# iv12-driver-board-v1b.net
KiCad netlist of a schematic drawn in EAGLE
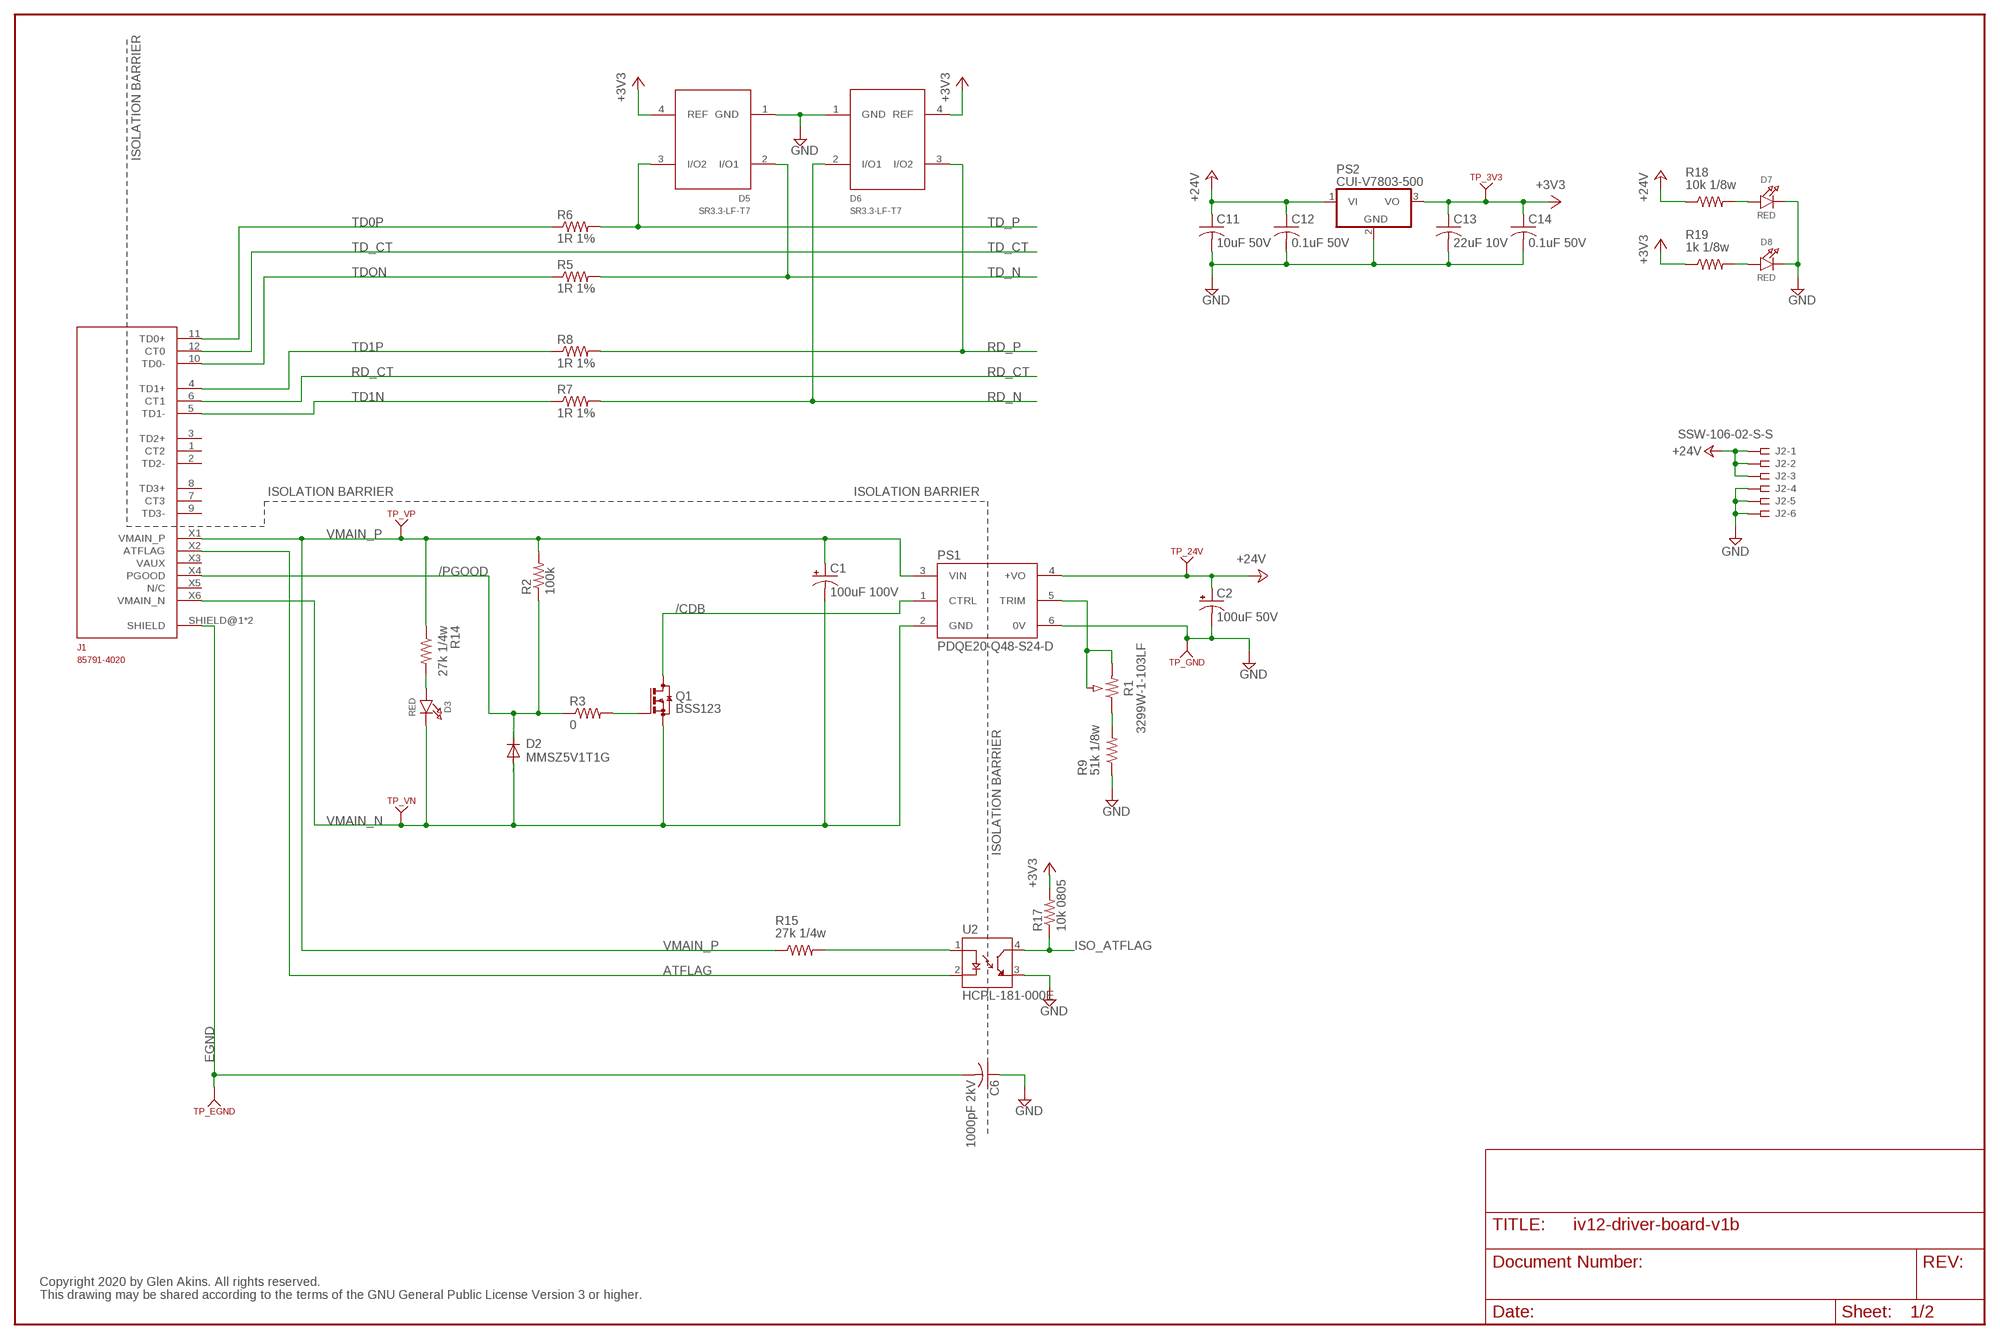
[diagram p0: schematic, sheet 1]
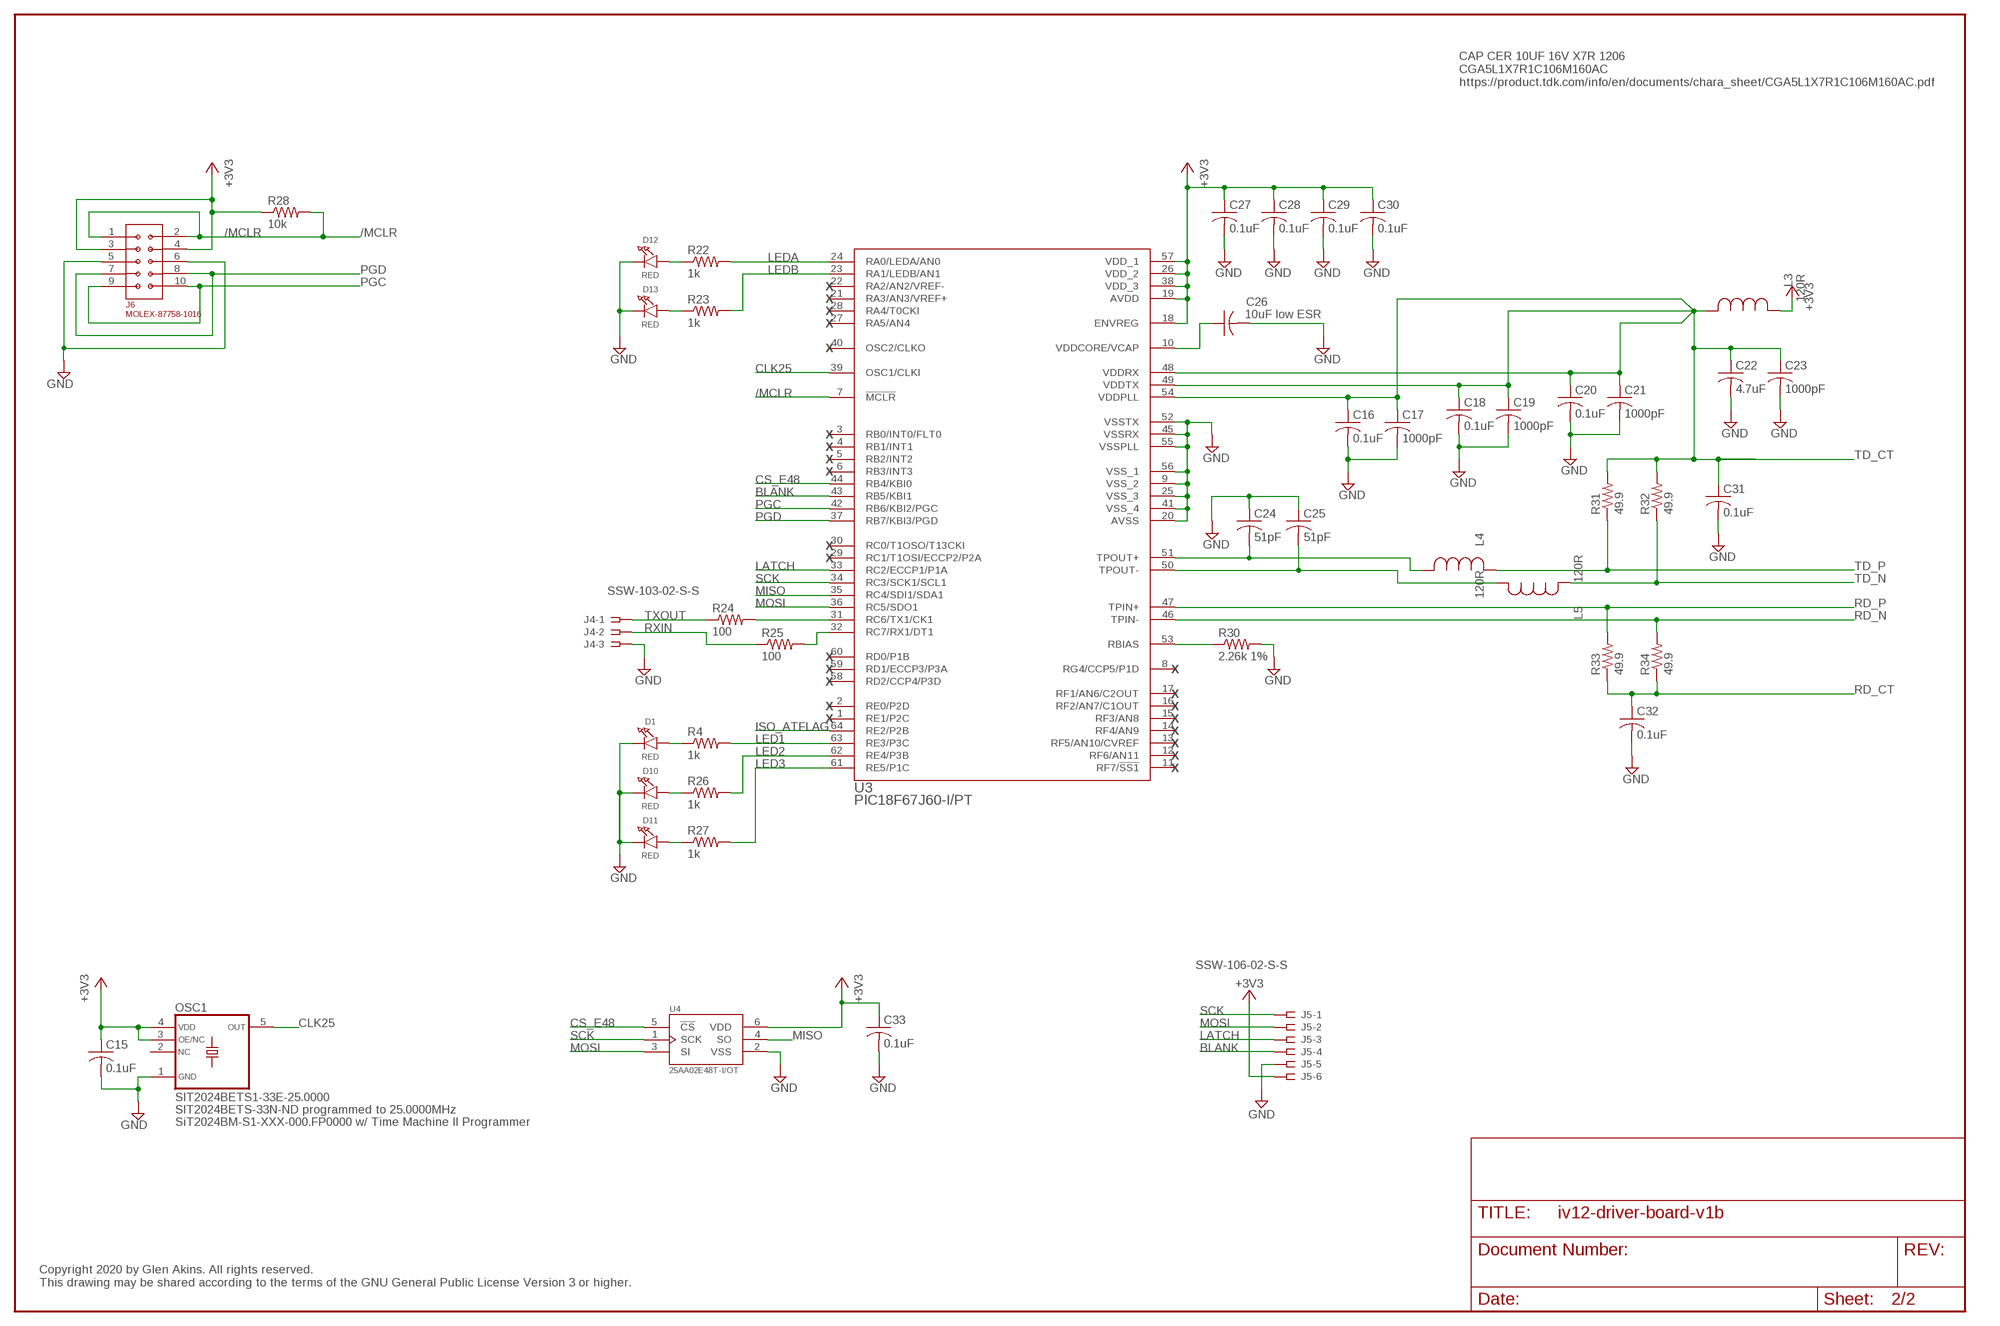
[diagram p1: schematic, sheet 2]

(export (version "E")
  (design (tool "Eeschema 10.0.6"))
  (components
    (comp (ref "C15")
      (value "0.1uF")
      (footprint "eagle-import:C0603")
      (libsource (lib "eagle-import") (part "C-USC0603"))
    )
    (comp (ref "C16")
      (value "0.1uF")
      (footprint "eagle-import:C0805")
      (libsource (lib "eagle-import") (part "C-USC0805"))
    )
    (comp (ref "C17")
      (value "1000pF")
      (footprint "eagle-import:C0805")
      (libsource (lib "eagle-import") (part "C-USC0805"))
    )
    (comp (ref "C18")
      (value "0.1uF")
      (footprint "eagle-import:C0805")
      (libsource (lib "eagle-import") (part "C-USC0805"))
    )
    (comp (ref "C19")
      (value "1000pF")
      (footprint "eagle-import:C0805")
      (libsource (lib "eagle-import") (part "C-USC0805"))
    )
    (comp (ref "C20")
      (value "0.1uF")
      (footprint "eagle-import:C0805")
      (libsource (lib "eagle-import") (part "C-USC0805"))
    )
    (comp (ref "C21")
      (value "1000pF")
      (footprint "eagle-import:C0805")
      (libsource (lib "eagle-import") (part "C-USC0805"))
    )
    (comp (ref "C22")
      (value "4.7uF")
      (footprint "eagle-import:C0805")
      (libsource (lib "eagle-import") (part "C-USC0805"))
    )
    (comp (ref "C23")
      (value "1000pF")
      (footprint "eagle-import:C0805")
      (libsource (lib "eagle-import") (part "C-USC0805"))
    )
    (comp (ref "C24")
      (value "51pF")
      (footprint "eagle-import:C0805")
      (libsource (lib "eagle-import") (part "C-USC0805"))
    )
    (comp (ref "C25")
      (value "51pF")
      (footprint "eagle-import:C0805")
      (libsource (lib "eagle-import") (part "C-USC0805"))
    )
    (comp (ref "C26")
      (value "10uF low ESR")
      (footprint "eagle-import:C1206")
      (libsource (lib "eagle-import") (part "resistor_C-USC1206"))
    )
    (comp (ref "C27")
      (value "0.1uF")
      (footprint "eagle-import:C0603")
      (libsource (lib "eagle-import") (part "C-USC0603"))
    )
    (comp (ref "C28")
      (value "0.1uF")
      (footprint "eagle-import:C0603")
      (libsource (lib "eagle-import") (part "C-USC0603"))
    )
    (comp (ref "C29")
      (value "0.1uF")
      (footprint "eagle-import:C0603")
      (libsource (lib "eagle-import") (part "C-USC0603"))
    )
    (comp (ref "C30")
      (value "0.1uF")
      (footprint "eagle-import:C0603")
      (libsource (lib "eagle-import") (part "C-USC0603"))
    )
    (comp (ref "C31")
      (value "0.1uF")
      (footprint "eagle-import:C0805")
      (libsource (lib "eagle-import") (part "C-USC0805"))
    )
    (comp (ref "C32")
      (value "0.1uF")
      (footprint "eagle-import:C0805")
      (libsource (lib "eagle-import") (part "C-USC0805"))
    )
    (comp (ref "C33")
      (value "0.1uF")
      (footprint "eagle-import:C0603")
      (libsource (lib "eagle-import") (part "C-USC0603"))
    )
    (comp (ref "D1")
      (value "RED")
      (footprint "eagle-import:CHIPLED_0805_NOOUTLINE")
      (libsource (lib "eagle-import") (part "LED0805_NOOUTLINE"))
    )
    (comp (ref "D10")
      (value "RED")
      (footprint "eagle-import:CHIPLED_0805_NOOUTLINE")
      (libsource (lib "eagle-import") (part "LED0805_NOOUTLINE"))
    )
    (comp (ref "D11")
      (value "RED")
      (footprint "eagle-import:CHIPLED_0805_NOOUTLINE")
      (libsource (lib "eagle-import") (part "LED0805_NOOUTLINE"))
    )
    (comp (ref "D12")
      (value "RED")
      (footprint "eagle-import:CHIPLED_0805_NOOUTLINE")
      (libsource (lib "eagle-import") (part "LED0805_NOOUTLINE"))
    )
    (comp (ref "D13")
      (value "RED")
      (footprint "eagle-import:CHIPLED_0805_NOOUTLINE")
      (libsource (lib "eagle-import") (part "LED0805_NOOUTLINE"))
    )
    (comp (ref "J4")
      (value "SSW-103-02-S-S")
      (footprint "eagle-import:SSW-103-02-S-S")
      (libsource (lib "eagle-import") (part "SSW-103-02-S-S"))
    )
    (comp (ref "J5")
      (value "SSW-106-02-S-S")
      (footprint "eagle-import:SSW-106-02-S-S")
      (libsource (lib "eagle-import") (part "SSW-106-02-S-S"))
    )
    (comp (ref "J6")
      (value "MOLEX-87758-1016")
      (footprint "eagle-import:CON-2MM-2X5")
      (fields (field (name "MFR") "MOLEX") (field (name "MFR_PART_NO") "87758-1016"))
      (libsource (lib "eagle-import") (part "CON-2MM-2X5-MOLEX-87758-1016"))
    )
    (comp (ref "L3")
      (value "120R")
      (footprint "eagle-import:IND_1608-M")
      (fields (field (name "MANUFACTURER_PART_NUMBER") "MMZ1608B121CTAH0"))
      (libsource (lib "eagle-import") (part "MMZ1608B121CTAH0IND_1608-M"))
    )
    (comp (ref "L4")
      (value "120R")
      (footprint "eagle-import:IND_1608-M")
      (fields (field (name "MANUFACTURER_PART_NUMBER") "MMZ1608B121CTAH0"))
      (libsource (lib "eagle-import") (part "MMZ1608B121CTAH0IND_1608-M"))
    )
    (comp (ref "L5")
      (value "120R")
      (footprint "eagle-import:IND_1608-M")
      (fields (field (name "MANUFACTURER_PART_NUMBER") "MMZ1608B121CTAH0"))
      (libsource (lib "eagle-import") (part "MMZ1608B121CTAH0IND_1608-M"))
    )
    (comp (ref "OSC1")
      (value "SIT2024BETS1-33E-25.0000")
      (footprint "eagle-import:SOT23-5")
      (libsource (lib "eagle-import") (part "SIT2024BETS1-33E-10.0000"))
    )
    (comp (ref "R4")
      (value "1k")
      (footprint "eagle-import:R0805")
      (libsource (lib "eagle-import") (part "R-US_R0805"))
    )
    (comp (ref "R22")
      (value "1k")
      (footprint "eagle-import:R0805")
      (libsource (lib "eagle-import") (part "R-US_R0805"))
    )
    (comp (ref "R23")
      (value "1k")
      (footprint "eagle-import:R0805")
      (libsource (lib "eagle-import") (part "R-US_R0805"))
    )
    (comp (ref "R24")
      (value "100")
      (footprint "eagle-import:R0805")
      (libsource (lib "eagle-import") (part "R-US_R0805"))
    )
    (comp (ref "R25")
      (value "100")
      (footprint "eagle-import:R0805")
      (libsource (lib "eagle-import") (part "R-US_R0805"))
    )
    (comp (ref "R26")
      (value "1k")
      (footprint "eagle-import:R0805")
      (libsource (lib "eagle-import") (part "R-US_R0805"))
    )
    (comp (ref "R27")
      (value "1k")
      (footprint "eagle-import:R0805")
      (libsource (lib "eagle-import") (part "R-US_R0805"))
    )
    (comp (ref "R28")
      (value "10k")
      (footprint "eagle-import:R0805")
      (libsource (lib "eagle-import") (part "R-US_R0805"))
    )
    (comp (ref "R30")
      (value "2.26k 1%")
      (footprint "eagle-import:R0805")
      (libsource (lib "eagle-import") (part "R-US_R0805"))
    )
    (comp (ref "R31")
      (value "49.9")
      (footprint "eagle-import:R0805")
      (libsource (lib "eagle-import") (part "R-US_R0805"))
    )
    (comp (ref "R32")
      (value "49.9")
      (footprint "eagle-import:R0805")
      (libsource (lib "eagle-import") (part "R-US_R0805"))
    )
    (comp (ref "R33")
      (value "49.9")
      (footprint "eagle-import:R0805")
      (libsource (lib "eagle-import") (part "R-US_R0805"))
    )
    (comp (ref "R34")
      (value "49.9")
      (footprint "eagle-import:R0805")
      (libsource (lib "eagle-import") (part "R-US_R0805"))
    )
    (comp (ref "U3")
      (value "PIC18F67J60-I/PT")
      (footprint "eagle-import:TQFP64_10X10MC")
      (fields (field (name "MANUFACTURER_PART_NUMBER") "PIC18F67J60IPT"))
      (libsource (lib "eagle-import") (part "PIC18F67J60-I/PT"))
    )
    (comp (ref "U4")
      (value "25AA02E48T-I/OT")
      (footprint "eagle-import:SOT95P270X145-6N")
      (fields (field (name "DIGI-KEY_PART_NUMBER") "25AA02E48T-I/OTCT-ND") (field (name "MF") "Microchip"))
      (libsource (lib "eagle-import") (part "25AA02E48T-I/OT"))
    )
    (comp (ref "C1")
      (value "100uF 100V")
      (footprint "eagle-import:E5-13")
      (libsource (lib "eagle-import") (part "CPOL-USE5-13"))
    )
    (comp (ref "C2")
      (value "100uF 50V")
      (footprint "eagle-import:E5-10,5")
      (libsource (lib "eagle-import") (part "CPOL-USE5-10.5"))
    )
    (comp (ref "C6")
      (value "1000pF 2kV")
      (footprint "eagle-import:C1206K")
      (libsource (lib "eagle-import") (part "C-USC1206K"))
    )
    (comp (ref "C11")
      (value "10uF 50V")
      (footprint "eagle-import:C1210K")
      (fields (field (name "MFR") "KEMET") (field (name "MFR_PART_NO") "C1210C106K5RACTU"))
      (libsource (lib "eagle-import") (part "C-USC1210K"))
    )
    (comp (ref "C12")
      (value "0.1uF 50V")
      (footprint "eagle-import:C0805")
      (fields (field (name "MFR") "KEMET") (field (name "MFR_PART_NO") "C1206S104M5RACTU"))
      (libsource (lib "eagle-import") (part "C-USC0805"))
    )
    (comp (ref "C13")
      (value "22uF 10V")
      (footprint "eagle-import:C1206K")
      (fields (field (name "MFR") "KEMET") (field (name "MFR_PART_NO") "C1206C226K8RAC7800"))
      (libsource (lib "eagle-import") (part "C-USC1206K"))
    )
    (comp (ref "C14")
      (value "0.1uF 50V")
      (footprint "eagle-import:C0805")
      (fields (field (name "MFR") "KEMET") (field (name "MFR_PART_NO") "C1206S104M5RACTU"))
      (libsource (lib "eagle-import") (part "C-USC0805"))
    )
    (comp (ref "D2")
      (value "MMSZ5V1T1G")
      (footprint "eagle-import:SOD123")
      (libsource (lib "eagle-import") (part "DIODE-SOD123"))
    )
    (comp (ref "D3")
      (value "RED")
      (footprint "eagle-import:CHIPLED_0805_NOOUTLINE")
      (libsource (lib "eagle-import") (part "LED0805_NOOUTLINE"))
    )
    (comp (ref "D5")
      (value "SR3.3-LF-T7")
      (footprint "eagle-import:SOT143B")
      (libsource (lib "eagle-import") (part "SR3.3-LF-T7"))
    )
    (comp (ref "D6")
      (value "SR3.3-LF-T7")
      (footprint "eagle-import:SOT143B")
      (libsource (lib "eagle-import") (part "SR3.3-LF-T7"))
    )
    (comp (ref "D7")
      (value "RED")
      (footprint "eagle-import:CHIPLED_0805_NOOUTLINE")
      (libsource (lib "eagle-import") (part "LED0805_NOOUTLINE"))
    )
    (comp (ref "D8")
      (value "RED")
      (footprint "eagle-import:CHIPLED_0805_NOOUTLINE")
      (libsource (lib "eagle-import") (part "LED0805_NOOUTLINE"))
    )
    (comp (ref "J1")
      (value "85791-4020")
      (footprint "eagle-import:85791-X020")
      (libsource (lib "eagle-import") (part "85791-4020"))
    )
    (comp (ref "J2")
      (value "SSW-106-02-S-S")
      (footprint "eagle-import:SSW-106-02-S-S")
      (libsource (lib "eagle-import") (part "SSW-106-02-S-S"))
    )
    (comp (ref "PS1")
      (value "PDQE20-Q48-S24-D")
      (footprint "eagle-import:CONV_PDQE20-Q48-S5-D")
      (fields
        (field (name "DIGI-KEY_PART_NUMBER") "102-6272-ND")
        (field (name "MF") "CUI Inc.")
        (field (name "MP") "PDQE20-Q48-S5-D")
      )
      (libsource (lib "eagle-import") (part "PDQE20-Q48-S5-D"))
    )
    (comp (ref "PS2")
      (value "CUI-V7803-500")
      (footprint "eagle-import:CUI-78XX-500")
      (libsource (lib "eagle-import") (part "CUI-V7803-500"))
    )
    (comp (ref "Q1")
      (value "BSS123")
      (footprint "eagle-import:SOT23")
      (libsource (lib "eagle-import") (part "BSS123"))
    )
    (comp (ref "R1")
      (value "3299W-1-103LF")
      (footprint "eagle-import:POT_3299W")
      (libsource (lib "eagle-import") (part "3299W-1-103LF"))
    )
    (comp (ref "R2")
      (value "100k")
      (footprint "eagle-import:R0805")
      (libsource (lib "eagle-import") (part "resistor_R-US_R0805"))
    )
    (comp (ref "R3")
      (value "0")
      (footprint "eagle-import:R0805")
      (libsource (lib "eagle-import") (part "resistor_R-US_R0805"))
    )
    (comp (ref "R5")
      (value "1R 1%")
      (footprint "eagle-import:R0805")
      (libsource (lib "eagle-import") (part "R-US_R0805"))
    )
    (comp (ref "R6")
      (value "1R 1%")
      (footprint "eagle-import:R0805")
      (libsource (lib "eagle-import") (part "R-US_R0805"))
    )
    (comp (ref "R7")
      (value "1R 1%")
      (footprint "eagle-import:R0805")
      (libsource (lib "eagle-import") (part "R-US_R0805"))
    )
    (comp (ref "R8")
      (value "1R 1%")
      (footprint "eagle-import:R0805")
      (libsource (lib "eagle-import") (part "R-US_R0805"))
    )
    (comp (ref "R9")
      (value "51k 1/8w")
      (footprint "eagle-import:R0805")
      (libsource (lib "eagle-import") (part "R-US_R0805"))
    )
    (comp (ref "R14")
      (value "27k 1/4w")
      (footprint "eagle-import:R1206")
      (libsource (lib "eagle-import") (part "R-US_R1206"))
    )
    (comp (ref "R15")
      (value "27k 1/4w")
      (footprint "eagle-import:R1206")
      (libsource (lib "eagle-import") (part "R-US_R1206"))
    )
    (comp (ref "R17")
      (value "10k 0805")
      (footprint "eagle-import:R0805")
      (libsource (lib "eagle-import") (part "resistor_R-US_R0805"))
    )
    (comp (ref "R18")
      (value "10k 1/8w")
      (footprint "eagle-import:R0805")
      (libsource (lib "eagle-import") (part "R-US_R0805"))
    )
    (comp (ref "R19")
      (value "1k 1/8w")
      (footprint "eagle-import:R0805")
      (libsource (lib "eagle-import") (part "R-US_R0805"))
    )
    (comp (ref "TP_3V3")
      (value "KEYSTONE_500X")
      (footprint "eagle-import:KEYSTONE_TP500X")
      (libsource (lib "eagle-import") (part "KEYSTONE_500X"))
    )
    (comp (ref "TP_24V")
      (value "KEYSTONE_500X")
      (footprint "eagle-import:KEYSTONE_TP500X")
      (libsource (lib "eagle-import") (part "KEYSTONE_500X"))
    )
    (comp (ref "TP_EGND")
      (value "KEYSTONE_500X")
      (footprint "eagle-import:KEYSTONE_TP500X")
      (libsource (lib "eagle-import") (part "KEYSTONE_500X"))
    )
    (comp (ref "TP_GND")
      (value "KEYSTONE_500X")
      (footprint "eagle-import:KEYSTONE_TP500X")
      (libsource (lib "eagle-import") (part "KEYSTONE_500X"))
    )
    (comp (ref "TP_VN")
      (value "KEYSTONE_500X")
      (footprint "eagle-import:KEYSTONE_TP500X")
      (libsource (lib "eagle-import") (part "KEYSTONE_500X"))
    )
    (comp (ref "TP_VP")
      (value "KEYSTONE_500X")
      (footprint "eagle-import:KEYSTONE_TP500X")
      (libsource (lib "eagle-import") (part "KEYSTONE_500X"))
    )
    (comp (ref "U2")
      (value "HCPL-181-000E")
      (footprint "eagle-import:SOIC254P675X240-4N")
      (fields (field (name "DIGI-KEY_PART_NUMBER") "516-1646-1-ND") (field (name "MF") "Broadcom Limited"))
      (libsource (lib "eagle-import") (part "HCPL-181-000E"))
    )
  )
  (nets
    (net (code "1") (name "+3V3") (class "Default")
      (node (ref "C13") (pin "1") (pinfunction "1_1") (pintype "passive"))
      (node (ref "C14") (pin "1") (pinfunction "1_1") (pintype "passive"))
      (node (ref "C15") (pin "1") (pinfunction "1_1") (pintype "passive"))
      (node (ref "C27") (pin "1") (pinfunction "1_1") (pintype "passive"))
      (node (ref "C28") (pin "1") (pinfunction "1_1") (pintype "passive"))
      (node (ref "C29") (pin "1") (pinfunction "1_1") (pintype "passive"))
      (node (ref "C30") (pin "1") (pinfunction "1_1") (pintype "passive"))
      (node (ref "C33") (pin "1") (pinfunction "1_1") (pintype "passive"))
      (node (ref "D5") (pin "4") (pinfunction "REF_4") (pintype "bidirectional"))
      (node (ref "D6") (pin "4") (pinfunction "REF_4") (pintype "bidirectional"))
      (node (ref "J5") (pin "6") (pinfunction "1_6") (pintype "passive"))
      (node (ref "J6") (pin "3") (pinfunction "3_3") (pintype "bidirectional"))
      (node (ref "J6") (pin "4") (pinfunction "4_4") (pintype "bidirectional"))
      (node (ref "L3") (pin "2") (pinfunction "2_2") (pintype "passive"))
      (node (ref "OSC1") (pin "3") (pinfunction "OE/NC_3") (pintype "bidirectional"))
      (node (ref "OSC1") (pin "4") (pinfunction "VDD_4") (pintype "bidirectional"))
      (node (ref "PS2") (pin "3") (pinfunction "VO_3") (pintype "passive"))
      (node (ref "R17") (pin "2") (pinfunction "2_2") (pintype "passive"))
      (node (ref "R19") (pin "1") (pinfunction "1_1") (pintype "passive"))
      (node (ref "R28") (pin "1") (pinfunction "1_1") (pintype "passive"))
      (node (ref "TP_3V3") (pin "1") (pinfunction "P$1_1") (pintype "bidirectional"))
      (node (ref "U3") (pin "18") (pinfunction "ENVREG_18") (pintype "passive"))
      (node (ref "U3") (pin "19") (pinfunction "AVDD_19") (pintype "passive"))
      (node (ref "U3") (pin "26") (pinfunction "VDD_2_26") (pintype "passive"))
      (node (ref "U3") (pin "38") (pinfunction "VDD_3_38") (pintype "passive"))
      (node (ref "U3") (pin "57") (pinfunction "VDD_1_57") (pintype "passive"))
      (node (ref "U4") (pin "6") (pinfunction "VDD_6") (pintype "power_in"))
    )
    (net (code "2") (name "+24V") (class "Default")
      (node (ref "C11") (pin "1") (pinfunction "1_1") (pintype "passive"))
      (node (ref "C12") (pin "1") (pinfunction "1_1") (pintype "passive"))
      (node (ref "C2") (pin "+") (pinfunction "+_+") (pintype "passive"))
      (node (ref "J2") (pin "1") (pinfunction "1_1") (pintype "passive"))
      (node (ref "J2") (pin "2") (pinfunction "1_2") (pintype "passive"))
      (node (ref "J2") (pin "3") (pinfunction "1_3") (pintype "passive"))
      (node (ref "PS1") (pin "4") (pinfunction "+VO_4") (pintype "output"))
      (node (ref "PS2") (pin "1") (pinfunction "VI_1") (pintype "input"))
      (node (ref "R18") (pin "1") (pinfunction "1_1") (pintype "passive"))
      (node (ref "TP_24V") (pin "1") (pinfunction "P$1_1") (pintype "bidirectional"))
    )
    (net (code "3") (name "ATFLAG") (class "Default")
      (node (ref "J1") (pin "X2") (pinfunction "ATFLAG_X2") (pintype "bidirectional"))
      (node (ref "U2") (pin "2") (pinfunction "CATHODE_2") (pintype "passive"))
    )
    (net (code "4") (name "BLANK") (class "Default")
      (node (ref "J5") (pin "4") (pinfunction "1_4") (pintype "passive"))
      (node (ref "U3") (pin "43") (pinfunction "RB5/KBI1_43") (pintype "passive"))
    )
    (net (code "5") (name "CLK25") (class "Default")
      (node (ref "OSC1") (pin "5") (pinfunction "OUT_5") (pintype "bidirectional"))
      (node (ref "U3") (pin "39") (pinfunction "OSC1/CLKI_39") (pintype "passive"))
    )
    (net (code "6") (name "CS_E48") (class "Default")
      (node (ref "U3") (pin "44") (pinfunction "RB4/KBI0_44") (pintype "passive"))
      (node (ref "U4") (pin "5") (pinfunction "~{CS}_5") (pintype "input"))
    )
    (net (code "7") (name "EGND") (class "Default")
      (node (ref "C6") (pin "2") (pinfunction "2_2") (pintype "passive"))
      (node (ref "J1") (pin "SHIELD@1") (pinfunction "SHIELD_SHIELD@1") (pintype "bidirectional"))
      (node (ref "J1") (pin "SHIELD@2") (pinfunction "SHIELD_SHIELD@2") (pintype "bidirectional"))
      (node (ref "TP_EGND") (pin "1") (pinfunction "P$1_1") (pintype "bidirectional"))
    )
    (net (code "8") (name "GND") (class "Default")
      (node (ref "C11") (pin "2") (pinfunction "2_2") (pintype "passive"))
      (node (ref "C12") (pin "2") (pinfunction "2_2") (pintype "passive"))
      (node (ref "C13") (pin "2") (pinfunction "2_2") (pintype "passive"))
      (node (ref "C14") (pin "2") (pinfunction "2_2") (pintype "passive"))
      (node (ref "C15") (pin "2") (pinfunction "2_2") (pintype "passive"))
      (node (ref "C16") (pin "2") (pinfunction "2_2") (pintype "passive"))
      (node (ref "C17") (pin "2") (pinfunction "2_2") (pintype "passive"))
      (node (ref "C18") (pin "2") (pinfunction "2_2") (pintype "passive"))
      (node (ref "C19") (pin "2") (pinfunction "2_2") (pintype "passive"))
      (node (ref "C2") (pin "-") (pinfunction "-_-") (pintype "passive"))
      (node (ref "C20") (pin "2") (pinfunction "2_2") (pintype "passive"))
      (node (ref "C21") (pin "2") (pinfunction "2_2") (pintype "passive"))
      (node (ref "C22") (pin "2") (pinfunction "2_2") (pintype "passive"))
      (node (ref "C23") (pin "2") (pinfunction "2_2") (pintype "passive"))
      (node (ref "C24") (pin "1") (pinfunction "1_1") (pintype "passive"))
      (node (ref "C25") (pin "1") (pinfunction "1_1") (pintype "passive"))
      (node (ref "C26") (pin "2") (pinfunction "2_2") (pintype "passive"))
      (node (ref "C27") (pin "2") (pinfunction "2_2") (pintype "passive"))
      (node (ref "C28") (pin "2") (pinfunction "2_2") (pintype "passive"))
      (node (ref "C29") (pin "2") (pinfunction "2_2") (pintype "passive"))
      (node (ref "C30") (pin "2") (pinfunction "2_2") (pintype "passive"))
      (node (ref "C31") (pin "2") (pinfunction "2_2") (pintype "passive"))
      (node (ref "C32") (pin "2") (pinfunction "2_2") (pintype "passive"))
      (node (ref "C33") (pin "2") (pinfunction "2_2") (pintype "passive"))
      (node (ref "C6") (pin "1") (pinfunction "1_1") (pintype "passive"))
      (node (ref "D1") (pin "C") (pinfunction "C_C") (pintype "passive"))
      (node (ref "D10") (pin "C") (pinfunction "C_C") (pintype "passive"))
      (node (ref "D11") (pin "C") (pinfunction "C_C") (pintype "passive"))
      (node (ref "D12") (pin "C") (pinfunction "C_C") (pintype "passive"))
      (node (ref "D13") (pin "C") (pinfunction "C_C") (pintype "passive"))
      (node (ref "D5") (pin "1") (pinfunction "GND_1") (pintype "bidirectional"))
      (node (ref "D6") (pin "1") (pinfunction "GND_1") (pintype "bidirectional"))
      (node (ref "D7") (pin "C") (pinfunction "C_C") (pintype "passive"))
      (node (ref "D8") (pin "C") (pinfunction "C_C") (pintype "passive"))
      (node (ref "J2") (pin "4") (pinfunction "1_4") (pintype "passive"))
      (node (ref "J2") (pin "5") (pinfunction "1_5") (pintype "passive"))
      (node (ref "J2") (pin "6") (pinfunction "1_6") (pintype "passive"))
      (node (ref "J4") (pin "3") (pinfunction "1_3") (pintype "passive"))
      (node (ref "J5") (pin "5") (pinfunction "1_5") (pintype "passive"))
      (node (ref "J6") (pin "5") (pinfunction "5_5") (pintype "bidirectional"))
      (node (ref "J6") (pin "6") (pinfunction "6_6") (pintype "bidirectional"))
      (node (ref "OSC1") (pin "1") (pinfunction "GND_1") (pintype "bidirectional"))
      (node (ref "PS1") (pin "6") (pinfunction "0V_6") (pintype "output"))
      (node (ref "PS2") (pin "2") (pinfunction "GND_2") (pintype "passive"))
      (node (ref "R30") (pin "2") (pinfunction "2_2") (pintype "passive"))
      (node (ref "R9") (pin "1") (pinfunction "1_1") (pintype "passive"))
      (node (ref "TP_GND") (pin "1") (pinfunction "P$1_1") (pintype "bidirectional"))
      (node (ref "U2") (pin "3") (pinfunction "EMITTER_3") (pintype "passive"))
      (node (ref "U3") (pin "20") (pinfunction "AVSS_20") (pintype "passive"))
      (node (ref "U3") (pin "25") (pinfunction "VSS_3_25") (pintype "passive"))
      (node (ref "U3") (pin "41") (pinfunction "VSS_4_41") (pintype "passive"))
      (node (ref "U3") (pin "45") (pinfunction "VSSRX_45") (pintype "passive"))
      (node (ref "U3") (pin "52") (pinfunction "VSSTX_52") (pintype "passive"))
      (node (ref "U3") (pin "55") (pinfunction "VSSPLL_55") (pintype "passive"))
      (node (ref "U3") (pin "56") (pinfunction "VSS_1_56") (pintype "passive"))
      (node (ref "U3") (pin "9") (pinfunction "VSS_2_9") (pintype "passive"))
      (node (ref "U4") (pin "2") (pinfunction "VSS_2") (pintype "power_in"))
    )
    (net (code "9") (name "ISO_ATFLAG") (class "Default")
      (node (ref "R17") (pin "1") (pinfunction "1_1") (pintype "passive"))
      (node (ref "U2") (pin "4") (pinfunction "COLLECTOR_4") (pintype "passive"))
      (node (ref "U3") (pin "64") (pinfunction "RE2/P2B_64") (pintype "passive"))
    )
    (net (code "10") (name "LATCH") (class "Default")
      (node (ref "J5") (pin "3") (pinfunction "1_3") (pintype "passive"))
      (node (ref "U3") (pin "33") (pinfunction "RC2/ECCP1/P1A_33") (pintype "passive"))
    )
    (net (code "11") (name "LED1") (class "Default")
      (node (ref "R4") (pin "2") (pinfunction "2_2") (pintype "passive"))
      (node (ref "U3") (pin "63") (pinfunction "RE3/P3C_63") (pintype "passive"))
    )
    (net (code "12") (name "LED2") (class "Default")
      (node (ref "R26") (pin "2") (pinfunction "2_2") (pintype "passive"))
      (node (ref "U3") (pin "62") (pinfunction "RE4/P3B_62") (pintype "passive"))
    )
    (net (code "13") (name "LED3") (class "Default")
      (node (ref "R27") (pin "2") (pinfunction "2_2") (pintype "passive"))
      (node (ref "U3") (pin "61") (pinfunction "RE5/P1C_61") (pintype "passive"))
    )
    (net (code "14") (name "LEDA") (class "Default")
      (node (ref "R22") (pin "2") (pinfunction "2_2") (pintype "passive"))
      (node (ref "U3") (pin "24") (pinfunction "RA0/LEDA/AN0_24") (pintype "passive"))
    )
    (net (code "15") (name "LEDB") (class "Default")
      (node (ref "R23") (pin "2") (pinfunction "2_2") (pintype "passive"))
      (node (ref "U3") (pin "23") (pinfunction "RA1/LEDB/AN1_23") (pintype "passive"))
    )
    (net (code "16") (name "MISO") (class "Default")
      (node (ref "U3") (pin "35") (pinfunction "RC4/SDI1/SDA1_35") (pintype "passive"))
      (node (ref "U4") (pin "4") (pinfunction "SO_4") (pintype "output"))
    )
    (net (code "17") (name "MOSI") (class "Default")
      (node (ref "J5") (pin "2") (pinfunction "1_2") (pintype "passive"))
      (node (ref "U3") (pin "36") (pinfunction "RC5/SDO1_36") (pintype "passive"))
      (node (ref "U4") (pin "3") (pinfunction "SI_3") (pintype "input"))
    )
    (net (code "18") (name "Net-(D1-PadA)") (class "Default")
      (node (ref "D1") (pin "A") (pinfunction "A_A") (pintype "passive"))
      (node (ref "R4") (pin "1") (pinfunction "1_1") (pintype "passive"))
    )
    (net (code "19") (name "Net-(D3-PadA)") (class "Default")
      (node (ref "D3") (pin "A") (pinfunction "A_A") (pintype "passive"))
      (node (ref "R14") (pin "2") (pinfunction "2_2") (pintype "passive"))
    )
    (net (code "20") (name "Net-(D7-PadA)") (class "Default")
      (node (ref "D7") (pin "A") (pinfunction "A_A") (pintype "passive"))
      (node (ref "R18") (pin "2") (pinfunction "2_2") (pintype "passive"))
    )
    (net (code "21") (name "Net-(D8-PadA)") (class "Default")
      (node (ref "D8") (pin "A") (pinfunction "A_A") (pintype "passive"))
      (node (ref "R19") (pin "2") (pinfunction "2_2") (pintype "passive"))
    )
    (net (code "22") (name "Net-(D10-PadA)") (class "Default")
      (node (ref "D10") (pin "A") (pinfunction "A_A") (pintype "passive"))
      (node (ref "R26") (pin "1") (pinfunction "1_1") (pintype "passive"))
    )
    (net (code "23") (name "Net-(D11-PadA)") (class "Default")
      (node (ref "D11") (pin "A") (pinfunction "A_A") (pintype "passive"))
      (node (ref "R27") (pin "1") (pinfunction "1_1") (pintype "passive"))
    )
    (net (code "24") (name "Net-(D12-PadA)") (class "Default")
      (node (ref "D12") (pin "A") (pinfunction "A_A") (pintype "passive"))
      (node (ref "R22") (pin "1") (pinfunction "1_1") (pintype "passive"))
    )
    (net (code "25") (name "Net-(D13-PadA)") (class "Default")
      (node (ref "D13") (pin "A") (pinfunction "A_A") (pintype "passive"))
      (node (ref "R23") (pin "1") (pinfunction "1_1") (pintype "passive"))
    )
    (net (code "26") (name "Net-(PS1-TRIM)") (class "Default")
      (node (ref "PS1") (pin "5") (pinfunction "TRIM_5") (pintype "passive"))
      (node (ref "R1") (pin "2") (pinfunction "2_2") (pintype "passive"))
      (node (ref "R1") (pin "3") (pinfunction "3_3") (pintype "passive"))
    )
    (net (code "27") (name "Net-(Q1-G)") (class "Default")
      (node (ref "Q1") (pin "1") (pinfunction "G_1") (pintype "passive"))
      (node (ref "R3") (pin "2") (pinfunction "2_2") (pintype "passive"))
    )
    (net (code "28") (name "Net-(R1-Pad1)") (class "Default")
      (node (ref "R1") (pin "1") (pinfunction "1_1") (pintype "passive"))
      (node (ref "R9") (pin "2") (pinfunction "2_2") (pintype "passive"))
    )
    (net (code "29") (name "Net-(U2-ANODE)") (class "Default")
      (node (ref "R15") (pin "2") (pinfunction "2_2") (pintype "passive"))
      (node (ref "U2") (pin "1") (pinfunction "ANODE_1") (pintype "passive"))
    )
    (net (code "30") (name "Net-(U3-RBIAS)") (class "Default")
      (node (ref "R30") (pin "1") (pinfunction "1_1") (pintype "passive"))
      (node (ref "U3") (pin "53") (pinfunction "RBIAS_53") (pintype "passive"))
    )
    (net (code "31") (name "Net-(U3-RC6{slash}TX1{slash}CK1)") (class "Default")
      (node (ref "R24") (pin "2") (pinfunction "2_2") (pintype "passive"))
      (node (ref "U3") (pin "31") (pinfunction "RC6/TX1/CK1_31") (pintype "passive"))
    )
    (net (code "32") (name "Net-(U3-RC7{slash}RX1{slash}DT1)") (class "Default")
      (node (ref "R25") (pin "2") (pinfunction "2_2") (pintype "passive"))
      (node (ref "U3") (pin "32") (pinfunction "RC7/RX1/DT1_32") (pintype "passive"))
    )
    (net (code "33") (name "Net-(U3-TPOUT+)") (class "Default")
      (node (ref "C24") (pin "2") (pinfunction "2_2") (pintype "passive"))
      (node (ref "L4") (pin "1") (pinfunction "1_1") (pintype "passive"))
      (node (ref "U3") (pin "51") (pinfunction "TPOUT+_51") (pintype "passive"))
    )
    (net (code "34") (name "Net-(U3-TPOUT-)") (class "Default")
      (node (ref "C25") (pin "2") (pinfunction "2_2") (pintype "passive"))
      (node (ref "L5") (pin "1") (pinfunction "1_1") (pintype "passive"))
      (node (ref "U3") (pin "50") (pinfunction "TPOUT-_50") (pintype "passive"))
    )
    (net (code "35") (name "Net-(U3-VDDCORE{slash}VCAP)") (class "Default")
      (node (ref "C26") (pin "1") (pinfunction "1_1") (pintype "passive"))
      (node (ref "U3") (pin "10") (pinfunction "VDDCORE/VCAP_10") (pintype "passive"))
    )
    (net (code "36") (name "PGC") (class "Default")
      (node (ref "J6") (pin "10") (pinfunction "10_10") (pintype "bidirectional"))
      (node (ref "J6") (pin "9") (pinfunction "9_9") (pintype "bidirectional"))
      (node (ref "U3") (pin "42") (pinfunction "RB6/KBI2/PGC_42") (pintype "passive"))
    )
    (net (code "37") (name "PGD") (class "Default")
      (node (ref "J6") (pin "7") (pinfunction "7_7") (pintype "bidirectional"))
      (node (ref "J6") (pin "8") (pinfunction "8_8") (pintype "bidirectional"))
      (node (ref "U3") (pin "37") (pinfunction "RB7/KBI3/PGD_37") (pintype "passive"))
    )
    (net (code "38") (name "RD_CT") (class "Default")
      (node (ref "C32") (pin "1") (pinfunction "1_1") (pintype "passive"))
      (node (ref "J1") (pin "6") (pinfunction "CT1_6") (pintype "bidirectional"))
      (node (ref "R33") (pin "1") (pinfunction "1_1") (pintype "passive"))
      (node (ref "R34") (pin "1") (pinfunction "1_1") (pintype "passive"))
    )
    (net (code "39") (name "RD_N") (class "Default")
      (node (ref "D6") (pin "2") (pinfunction "I/O1_2") (pintype "bidirectional"))
      (node (ref "R34") (pin "2") (pinfunction "2_2") (pintype "passive"))
      (node (ref "R7") (pin "2") (pinfunction "2_2") (pintype "passive"))
      (node (ref "U3") (pin "46") (pinfunction "TPIN-_46") (pintype "passive"))
    )
    (net (code "40") (name "RD_P") (class "Default")
      (node (ref "D6") (pin "3") (pinfunction "I/O2_3") (pintype "bidirectional"))
      (node (ref "R33") (pin "2") (pinfunction "2_2") (pintype "passive"))
      (node (ref "R8") (pin "2") (pinfunction "2_2") (pintype "passive"))
      (node (ref "U3") (pin "47") (pinfunction "TPIN+_47") (pintype "passive"))
    )
    (net (code "41") (name "RXIN") (class "Default")
      (node (ref "J4") (pin "2") (pinfunction "1_2") (pintype "passive"))
      (node (ref "R25") (pin "1") (pinfunction "1_1") (pintype "passive"))
    )
    (net (code "42") (name "SCK") (class "Default")
      (node (ref "J5") (pin "1") (pinfunction "1_1") (pintype "passive"))
      (node (ref "U3") (pin "34") (pinfunction "RC3/SCK1/SCL1_34") (pintype "passive"))
      (node (ref "U4") (pin "1") (pinfunction "SCK_1") (pintype "input"))
    )
    (net (code "43") (name "TD0P") (class "Default")
      (node (ref "J1") (pin "11") (pinfunction "TD0+_11") (pintype "bidirectional"))
      (node (ref "R6") (pin "1") (pinfunction "1_1") (pintype "passive"))
    )
    (net (code "44") (name "TD1N") (class "Default")
      (node (ref "J1") (pin "5") (pinfunction "TD1-_5") (pintype "bidirectional"))
      (node (ref "R7") (pin "1") (pinfunction "1_1") (pintype "passive"))
    )
    (net (code "45") (name "TD1P") (class "Default")
      (node (ref "J1") (pin "4") (pinfunction "TD1+_4") (pintype "bidirectional"))
      (node (ref "R8") (pin "1") (pinfunction "1_1") (pintype "passive"))
    )
    (net (code "46") (name "TDON") (class "Default")
      (node (ref "J1") (pin "10") (pinfunction "TD0-_10") (pintype "bidirectional"))
      (node (ref "R5") (pin "1") (pinfunction "1_1") (pintype "passive"))
    )
    (net (code "47") (name "TD_CT") (class "Default")
      (node (ref "C16") (pin "1") (pinfunction "1_1") (pintype "passive"))
      (node (ref "C17") (pin "1") (pinfunction "1_1") (pintype "passive"))
      (node (ref "C18") (pin "1") (pinfunction "1_1") (pintype "passive"))
      (node (ref "C19") (pin "1") (pinfunction "1_1") (pintype "passive"))
      (node (ref "C20") (pin "1") (pinfunction "1_1") (pintype "passive"))
      (node (ref "C21") (pin "1") (pinfunction "1_1") (pintype "passive"))
      (node (ref "C22") (pin "1") (pinfunction "1_1") (pintype "passive"))
      (node (ref "C23") (pin "1") (pinfunction "1_1") (pintype "passive"))
      (node (ref "C31") (pin "1") (pinfunction "1_1") (pintype "passive"))
      (node (ref "J1") (pin "12") (pinfunction "CT0_12") (pintype "bidirectional"))
      (node (ref "L3") (pin "1") (pinfunction "1_1") (pintype "passive"))
      (node (ref "R31") (pin "2") (pinfunction "2_2") (pintype "passive"))
      (node (ref "R32") (pin "2") (pinfunction "2_2") (pintype "passive"))
      (node (ref "U3") (pin "48") (pinfunction "VDDRX_48") (pintype "passive"))
      (node (ref "U3") (pin "49") (pinfunction "VDDTX_49") (pintype "passive"))
      (node (ref "U3") (pin "54") (pinfunction "VDDPLL_54") (pintype "passive"))
    )
    (net (code "48") (name "TD_N") (class "Default")
      (node (ref "D5") (pin "2") (pinfunction "I/O1_2") (pintype "bidirectional"))
      (node (ref "L5") (pin "2") (pinfunction "2_2") (pintype "passive"))
      (node (ref "R32") (pin "1") (pinfunction "1_1") (pintype "passive"))
      (node (ref "R5") (pin "2") (pinfunction "2_2") (pintype "passive"))
    )
    (net (code "49") (name "TD_P") (class "Default")
      (node (ref "D5") (pin "3") (pinfunction "I/O2_3") (pintype "bidirectional"))
      (node (ref "L4") (pin "2") (pinfunction "2_2") (pintype "passive"))
      (node (ref "R31") (pin "1") (pinfunction "1_1") (pintype "passive"))
      (node (ref "R6") (pin "2") (pinfunction "2_2") (pintype "passive"))
    )
    (net (code "50") (name "TXOUT") (class "Default")
      (node (ref "J4") (pin "1") (pinfunction "1_1") (pintype "passive"))
      (node (ref "R24") (pin "1") (pinfunction "1_1") (pintype "passive"))
    )
    (net (code "51") (name "VMAIN_N") (class "Default")
      (node (ref "C1") (pin "-") (pinfunction "-_-") (pintype "passive"))
      (node (ref "D2") (pin "A") (pinfunction "A_A") (pintype "passive"))
      (node (ref "D3") (pin "C") (pinfunction "C_C") (pintype "passive"))
      (node (ref "J1") (pin "X6") (pinfunction "VMAIN_N_X6") (pintype "bidirectional"))
      (node (ref "PS1") (pin "2") (pinfunction "GND_2") (pintype "power_in"))
      (node (ref "Q1") (pin "2") (pinfunction "S_2") (pintype "passive"))
      (node (ref "TP_VN") (pin "1") (pinfunction "P$1_1") (pintype "bidirectional"))
    )
    (net (code "52") (name "VMAIN_P") (class "Default")
      (node (ref "C1") (pin "+") (pinfunction "+_+") (pintype "passive"))
      (node (ref "J1") (pin "X1") (pinfunction "VMAIN_P_X1") (pintype "bidirectional"))
      (node (ref "PS1") (pin "3") (pinfunction "VIN_3") (pintype "input"))
      (node (ref "R14") (pin "1") (pinfunction "1_1") (pintype "passive"))
      (node (ref "R15") (pin "1") (pinfunction "1_1") (pintype "passive"))
      (node (ref "R2") (pin "2") (pinfunction "2_2") (pintype "passive"))
      (node (ref "TP_VP") (pin "1") (pinfunction "P$1_1") (pintype "bidirectional"))
    )
    (net (code "53") (name "unconnected-(J1-CT2-Pad1)") (class "Default")
      (node (ref "J1") (pin "1") (pinfunction "CT2_1") (pintype "bidirectional"))
    )
    (net (code "54") (name "unconnected-(J1-CT3-Pad7)") (class "Default")
      (node (ref "J1") (pin "7") (pinfunction "CT3_7") (pintype "bidirectional"))
    )
    (net (code "55") (name "unconnected-(J1-N{slash}C-PadX5)") (class "Default")
      (node (ref "J1") (pin "X5") (pinfunction "N/C_X5") (pintype "bidirectional"))
    )
    (net (code "56") (name "unconnected-(J1-TD2+-Pad3)") (class "Default")
      (node (ref "J1") (pin "3") (pinfunction "TD2+_3") (pintype "bidirectional"))
    )
    (net (code "57") (name "unconnected-(J1-TD2--Pad2)") (class "Default")
      (node (ref "J1") (pin "2") (pinfunction "TD2-_2") (pintype "bidirectional"))
    )
    (net (code "58") (name "unconnected-(J1-TD3+-Pad8)") (class "Default")
      (node (ref "J1") (pin "8") (pinfunction "TD3+_8") (pintype "bidirectional"))
    )
    (net (code "59") (name "unconnected-(J1-TD3--Pad9)") (class "Default")
      (node (ref "J1") (pin "9") (pinfunction "TD3-_9") (pintype "bidirectional"))
    )
    (net (code "60") (name "unconnected-(J1-VAUX-PadX3)") (class "Default")
      (node (ref "J1") (pin "X3") (pinfunction "VAUX_X3") (pintype "bidirectional"))
    )
    (net (code "61") (name "unconnected-(OSC1-NC-Pad2)") (class "Default")
      (node (ref "OSC1") (pin "2") (pinfunction "NC_2") (pintype "bidirectional"))
    )
    (net (code "62") (name "unconnected-(U3-OSC2{slash}CLKO-Pad40)") (class "Default")
      (node (ref "U3") (pin "40") (pinfunction "OSC2/CLKO_40") (pintype "passive"))
    )
    (net (code "63") (name "unconnected-(U3-RA2{slash}AN2{slash}VREF--Pad22)") (class "Default")
      (node (ref "U3") (pin "22") (pinfunction "RA2/AN2/VREF-_22") (pintype "passive"))
    )
    (net (code "64") (name "unconnected-(U3-RA3{slash}AN3{slash}VREF+-Pad21)") (class "Default")
      (node (ref "U3") (pin "21") (pinfunction "RA3/AN3/VREF+_21") (pintype "passive"))
    )
    (net (code "65") (name "unconnected-(U3-RA4{slash}T0CKI-Pad28)") (class "Default")
      (node (ref "U3") (pin "28") (pinfunction "RA4/T0CKI_28") (pintype "passive"))
    )
    (net (code "66") (name "unconnected-(U3-RA5{slash}AN4-Pad27)") (class "Default")
      (node (ref "U3") (pin "27") (pinfunction "RA5/AN4_27") (pintype "passive"))
    )
    (net (code "67") (name "unconnected-(U3-RB0{slash}INT0{slash}FLT0-Pad3)") (class "Default")
      (node (ref "U3") (pin "3") (pinfunction "RB0/INT0/FLT0_3") (pintype "passive"))
    )
    (net (code "68") (name "unconnected-(U3-RB1{slash}INT1-Pad4)") (class "Default")
      (node (ref "U3") (pin "4") (pinfunction "RB1/INT1_4") (pintype "passive"))
    )
    (net (code "69") (name "unconnected-(U3-RB2{slash}INT2-Pad5)") (class "Default")
      (node (ref "U3") (pin "5") (pinfunction "RB2/INT2_5") (pintype "passive"))
    )
    (net (code "70") (name "unconnected-(U3-RB3{slash}INT3-Pad6)") (class "Default")
      (node (ref "U3") (pin "6") (pinfunction "RB3/INT3_6") (pintype "passive"))
    )
    (net (code "71") (name "unconnected-(U3-RC0{slash}T1OSO{slash}T13CKI-Pad30)") (class "Default")
      (node (ref "U3") (pin "30") (pinfunction "RC0/T1OSO/T13CKI_30") (pintype "passive"))
    )
    (net (code "72") (name "unconnected-(U3-RC1{slash}T1OSI{slash}ECCP2{slash}P2A-Pad29)") (class "Default")
      (node (ref "U3") (pin "29") (pinfunction "RC1/T1OSI/ECCP2/P2A_29") (pintype "passive"))
    )
    (net (code "73") (name "unconnected-(U3-RD0{slash}P1B-Pad60)") (class "Default")
      (node (ref "U3") (pin "60") (pinfunction "RD0/P1B_60") (pintype "passive"))
    )
    (net (code "74") (name "unconnected-(U3-RD1{slash}ECCP3{slash}P3A-Pad59)") (class "Default")
      (node (ref "U3") (pin "59") (pinfunction "RD1/ECCP3/P3A_59") (pintype "passive"))
    )
    (net (code "75") (name "unconnected-(U3-RD2{slash}CCP4{slash}P3D-Pad58)") (class "Default")
      (node (ref "U3") (pin "58") (pinfunction "RD2/CCP4/P3D_58") (pintype "passive"))
    )
    (net (code "76") (name "unconnected-(U3-RE0{slash}P2D-Pad2)") (class "Default")
      (node (ref "U3") (pin "2") (pinfunction "RE0/P2D_2") (pintype "passive"))
    )
    (net (code "77") (name "unconnected-(U3-RE1{slash}P2C-Pad1)") (class "Default")
      (node (ref "U3") (pin "1") (pinfunction "RE1/P2C_1") (pintype "passive"))
    )
    (net (code "78") (name "unconnected-(U3-RF1{slash}AN6{slash}C2OUT-Pad17)") (class "Default")
      (node (ref "U3") (pin "17") (pinfunction "RF1/AN6/C2OUT_17") (pintype "passive"))
    )
    (net (code "79") (name "unconnected-(U3-RF2{slash}AN7{slash}C1OUT-Pad16)") (class "Default")
      (node (ref "U3") (pin "16") (pinfunction "RF2/AN7/C1OUT_16") (pintype "passive"))
    )
    (net (code "80") (name "unconnected-(U3-RF3{slash}AN8-Pad15)") (class "Default")
      (node (ref "U3") (pin "15") (pinfunction "RF3/AN8_15") (pintype "passive"))
    )
    (net (code "81") (name "unconnected-(U3-RF4{slash}AN9-Pad14)") (class "Default")
      (node (ref "U3") (pin "14") (pinfunction "RF4/AN9_14") (pintype "passive"))
    )
    (net (code "82") (name "unconnected-(U3-RF5{slash}AN10{slash}CVREF-Pad13)") (class "Default")
      (node (ref "U3") (pin "13") (pinfunction "RF5/AN10/CVREF_13") (pintype "passive"))
    )
    (net (code "83") (name "unconnected-(U3-RF6{slash}AN11-Pad12)") (class "Default")
      (node (ref "U3") (pin "12") (pinfunction "RF6/AN11_12") (pintype "passive"))
    )
    (net (code "84") (name "unconnected-(U3-RF7{slash}~{SS1}-Pad11)") (class "Default")
      (node (ref "U3") (pin "11") (pinfunction "RF7/~{SS1}_11") (pintype "passive"))
    )
    (net (code "85") (name "unconnected-(U3-RG4{slash}CCP5{slash}P1D-Pad8)") (class "Default")
      (node (ref "U3") (pin "8") (pinfunction "RG4/CCP5/P1D_8") (pintype "passive"))
    )
    (net (code "86") (name "{slash}CDB") (class "Default")
      (node (ref "PS1") (pin "1") (pinfunction "CTRL_1") (pintype "input"))
      (node (ref "Q1") (pin "3") (pinfunction "D_3") (pintype "passive"))
    )
    (net (code "87") (name "{slash}MCLR") (class "Default")
      (node (ref "J6") (pin "1") (pinfunction "1_1") (pintype "bidirectional"))
      (node (ref "J6") (pin "2") (pinfunction "2_2") (pintype "bidirectional"))
      (node (ref "R28") (pin "2") (pinfunction "2_2") (pintype "passive"))
      (node (ref "U3") (pin "7") (pinfunction "~{MCLR}_7") (pintype "passive"))
    )
    (net (code "88") (name "{slash}PGOOD") (class "Default")
      (node (ref "D2") (pin "C") (pinfunction "C_C") (pintype "passive"))
      (node (ref "J1") (pin "X4") (pinfunction "PGOOD_X4") (pintype "bidirectional"))
      (node (ref "R2") (pin "1") (pinfunction "1_1") (pintype "passive"))
      (node (ref "R3") (pin "1") (pinfunction "1_1") (pintype "passive"))
    )
  )
)
